# controllerboost.net
KiCad netlist of a schematic drawn in EAGLE
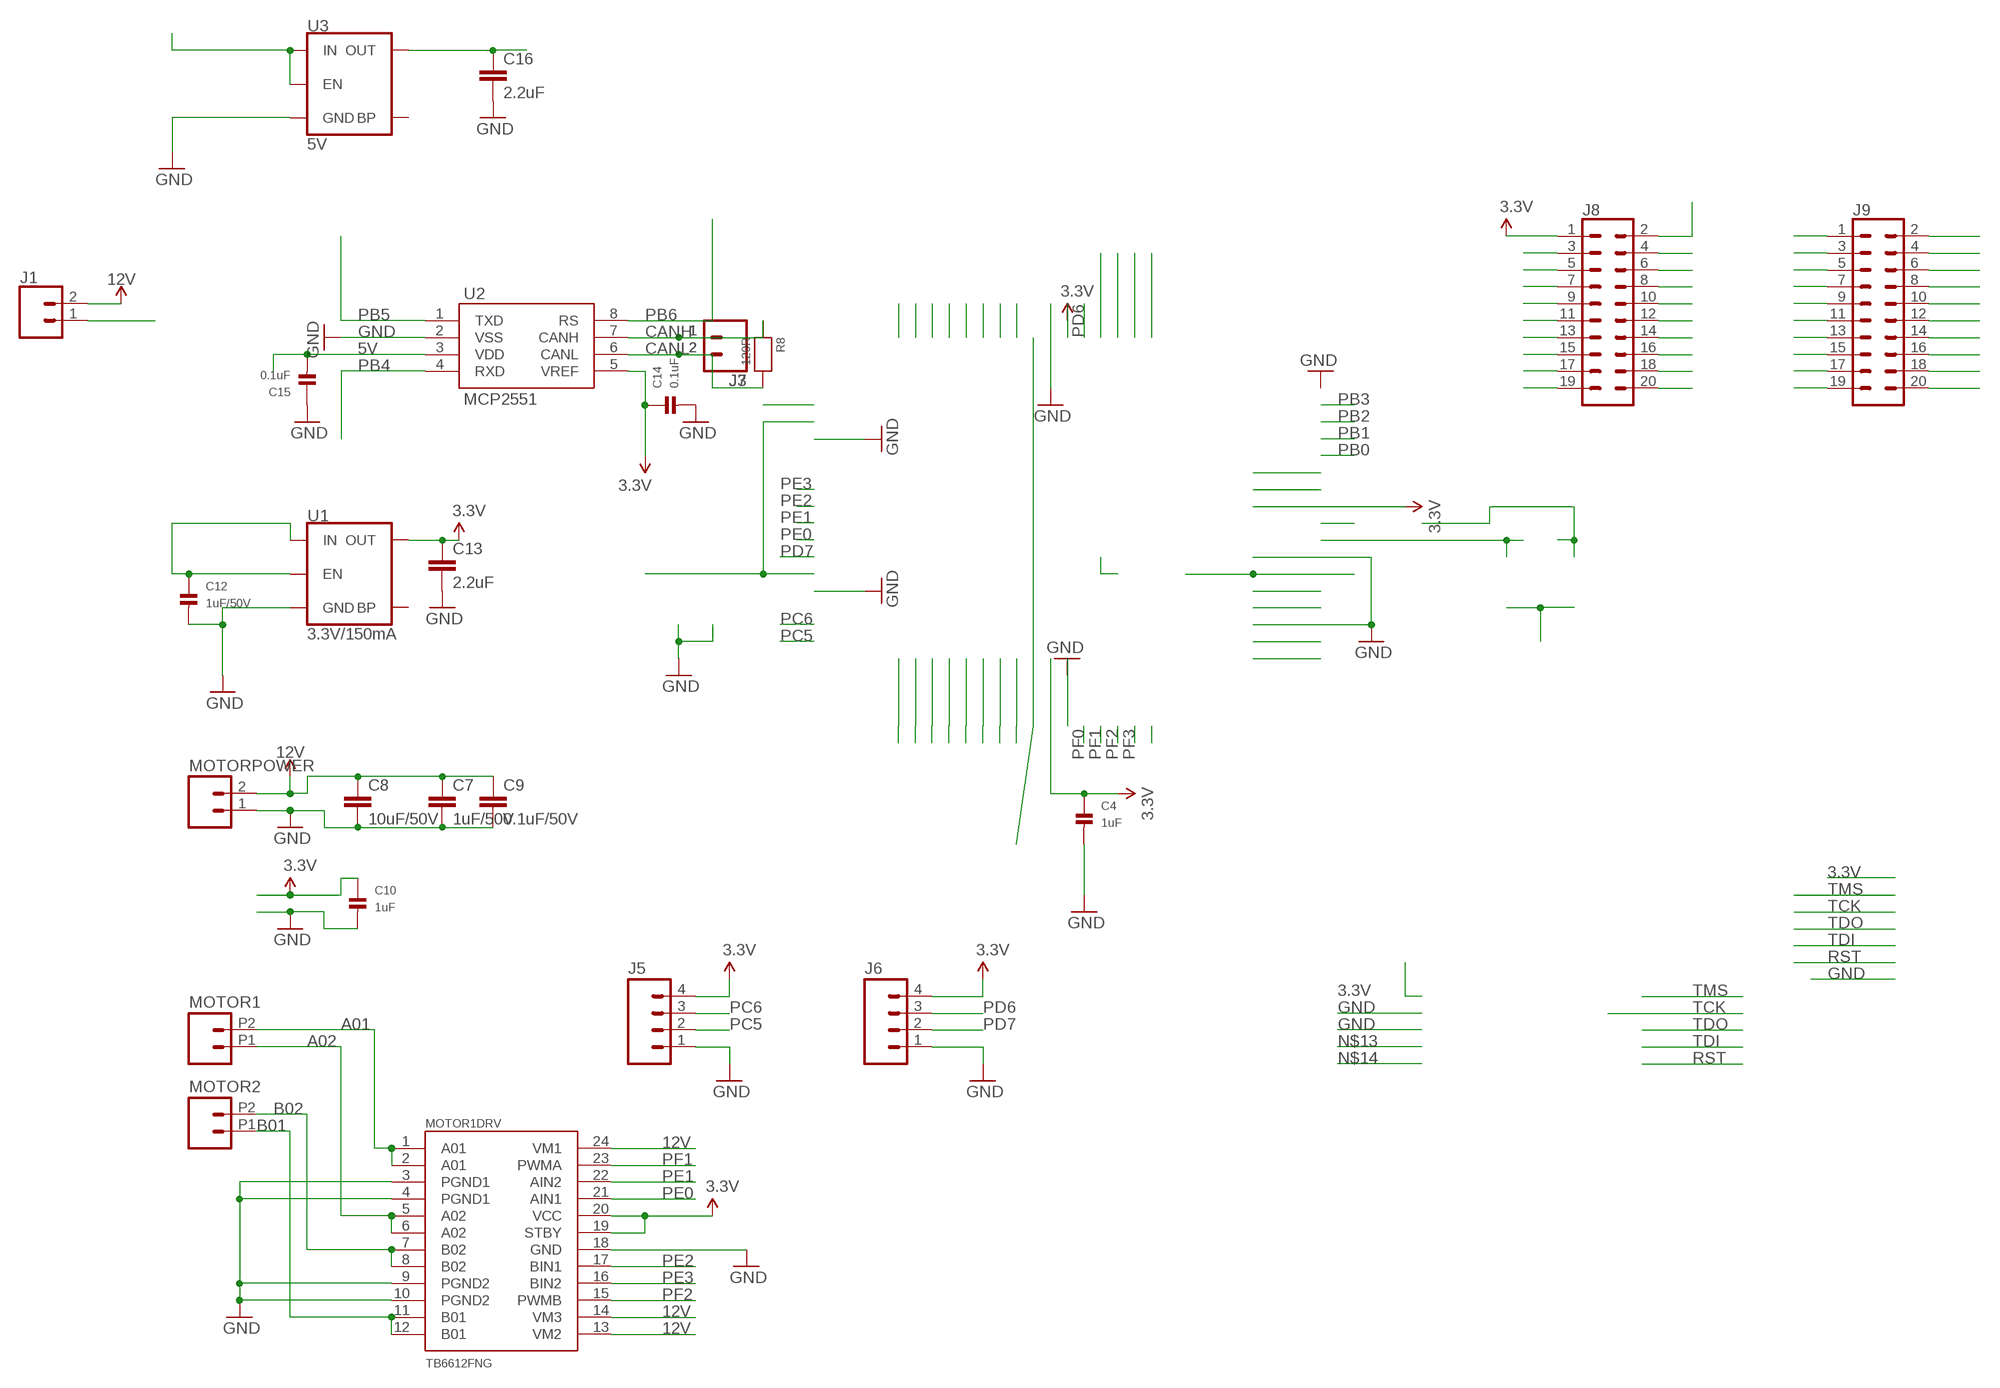
[diagram p0: schematic, sheet 1]

(export (version "E")
  (design (tool "Eeschema 10.0.6"))
  (components
    (comp (ref "C4")
      (value "1uF")
      (footprint "eagle-import:_0603MP")
      (libsource (lib "eagle-import") (part "CAP_CERAMIC_0603MP"))
    )
    (comp (ref "C7")
      (value "1uF/50V")
      (footprint "eagle-import:0603-CAP")
      (libsource (lib "eagle-import") (part "0.1UF-25V(+80/-20%)(0603)"))
    )
    (comp (ref "C8")
      (value "10uF/50V")
      (footprint "eagle-import:0805-CAP")
      (libsource (lib "eagle-import") (part "1.0UF-25V-+80/-20(0805){dblquote}"))
    )
    (comp (ref "C9")
      (value "0.1uF/50V")
      (footprint "eagle-import:0603-CAP")
      (libsource (lib "eagle-import") (part "0.1UF-25V(+80/-20%)(0603)"))
    )
    (comp (ref "C10")
      (value "1uF")
      (footprint "eagle-import:_0603MP")
      (libsource (lib "eagle-import") (part "CAP_CERAMIC_0603MP"))
    )
    (comp (ref "C12")
      (value "1uF/50V")
      (footprint "eagle-import:_0603MP")
      (libsource (lib "eagle-import") (part "CAP_CERAMIC_0603MP"))
    )
    (comp (ref "C13")
      (value "2.2uF")
      (footprint "eagle-import:0805")
      (libsource (lib "eagle-import") (part "2.2UF-0805-25V-(+80/-20%)"))
    )
    (comp (ref "C14")
      (value "0.1uF")
      (footprint "eagle-import:_0603MP")
      (libsource (lib "eagle-import") (part "CAP_CERAMIC_0603MP"))
    )
    (comp (ref "C15")
      (value "0.1uF")
      (footprint "eagle-import:_0603MP")
      (libsource (lib "eagle-import") (part "CAP_CERAMIC_0603MP"))
    )
    (comp (ref "C16")
      (value "2.2uF")
      (footprint "eagle-import:0805")
      (libsource (lib "eagle-import") (part "2.2UF-0805-25V-(+80/-20%)"))
    )
    (comp (ref "J1")
      (value "CONN_02")
      (footprint "eagle-import:1X02")
      (libsource (lib "eagle-import") (part "CONN_02"))
    )
    (comp (ref "J3")
      (value "CONN_02")
      (footprint "eagle-import:1X02")
      (libsource (lib "eagle-import") (part "CONN_02"))
    )
    (comp (ref "J5")
      (value "M04PTH")
      (footprint "eagle-import:1X04")
      (libsource (lib "eagle-import") (part "M04PTH"))
    )
    (comp (ref "J6")
      (value "M04PTH")
      (footprint "eagle-import:1X04")
      (libsource (lib "eagle-import") (part "M04PTH"))
    )
    (comp (ref "J7")
      (value "CONN_02")
      (footprint "eagle-import:1X02")
      (libsource (lib "eagle-import") (part "CONN_02"))
    )
    (comp (ref "J8")
      (value "CONN_10X2")
      (footprint "eagle-import:2X10")
      (libsource (lib "eagle-import") (part "CONN_10X2"))
    )
    (comp (ref "J9")
      (value "CONN_10X2")
      (footprint "eagle-import:2X10")
      (libsource (lib "eagle-import") (part "CONN_10X2"))
    )
    (comp (ref "MOTOR1")
      (value "M022.54MM_SCREWTERM")
      (footprint "eagle-import:1X02_2.54_SCREWTERM@1")
      (libsource (lib "eagle-import") (part "M022.54MM_SCREWTERM"))
    )
    (comp (ref "MOTOR1DRV")
      (value "TB6612FNG")
      (footprint "eagle-import:SSOP24")
      (libsource (lib "eagle-import") (part "TB6612FNG"))
    )
    (comp (ref "MOTOR2")
      (value "M022.54MM_SCREWTERM")
      (footprint "eagle-import:1X02_2.54_SCREWTERM@1")
      (libsource (lib "eagle-import") (part "M022.54MM_SCREWTERM"))
    )
    (comp (ref "MOTORPOWER")
      (value "M02PTH")
      (footprint "eagle-import:1X02@1")
      (libsource (lib "eagle-import") (part "M02PTH"))
    )
    (comp (ref "R8")
      (value "120R")
      (footprint "eagle-import:_0603MP")
      (libsource (lib "eagle-import") (part "RESISTOR_0603MP"))
    )
    (comp (ref "U1")
      (value "3.3V/150mA")
      (footprint "eagle-import:SOT23-5")
      (libsource (lib "eagle-import") (part "V_REG_MIC52053.3V"))
    )
    (comp (ref "U2")
      (value "MCP2551")
      (footprint "eagle-import:SO08")
      (libsource (lib "eagle-import") (part "MCP2551"))
    )
    (comp (ref "U3")
      (value "5V")
      (footprint "eagle-import:SOT23-5")
      (libsource (lib "eagle-import") (part "V_REG_MIC52053.3V"))
    )
  )
  (nets
    (net (code "1") (name "/5V") (class "Default")
      (node (ref "C15") (pin "2") (pinfunction "P$2_2") (pintype "passive"))
      (node (ref "C16") (pin "1") (pinfunction "1_1") (pintype "passive"))
      (node (ref "J8") (pin "2") (pinfunction "2_2") (pintype "passive"))
      (node (ref "U2") (pin "3") (pinfunction "VDD_3") (pintype "bidirectional"))
      (node (ref "U3") (pin "5") (pinfunction "OUT_5") (pintype "passive"))
    )
    (net (code "2") (name "/A01") (class "Default")
      (node (ref "MOTOR1") (pin "P2") (pinfunction "2_P2") (pintype "passive"))
      (node (ref "MOTOR1DRV") (pin "1") (pinfunction "A01_1") (pintype "bidirectional"))
      (node (ref "MOTOR1DRV") (pin "2") (pinfunction "A01_2") (pintype "bidirectional"))
    )
    (net (code "3") (name "/A02") (class "Default")
      (node (ref "MOTOR1") (pin "P1") (pinfunction "1_P1") (pintype "passive"))
      (node (ref "MOTOR1DRV") (pin "5") (pinfunction "A02_5") (pintype "bidirectional"))
      (node (ref "MOTOR1DRV") (pin "6") (pinfunction "A02_6") (pintype "bidirectional"))
    )
    (net (code "4") (name "/B01") (class "Default")
      (node (ref "MOTOR1DRV") (pin "11") (pinfunction "B01_11") (pintype "bidirectional"))
      (node (ref "MOTOR1DRV") (pin "12") (pinfunction "B01_12") (pintype "bidirectional"))
      (node (ref "MOTOR2") (pin "P1") (pinfunction "1_P1") (pintype "passive"))
    )
    (net (code "5") (name "/B02") (class "Default")
      (node (ref "MOTOR1DRV") (pin "7") (pinfunction "B02_7") (pintype "bidirectional"))
      (node (ref "MOTOR1DRV") (pin "8") (pinfunction "B02_8") (pintype "bidirectional"))
      (node (ref "MOTOR2") (pin "P2") (pinfunction "2_P2") (pintype "passive"))
    )
    (net (code "6") (name "/CANH") (class "Default")
      (node (ref "J3") (pin "1") (pinfunction "1_1") (pintype "passive"))
      (node (ref "J7") (pin "1") (pinfunction "1_1") (pintype "passive"))
      (node (ref "R8") (pin "1") (pinfunction "1_1") (pintype "passive"))
      (node (ref "U2") (pin "7") (pinfunction "CANH_7") (pintype "bidirectional"))
    )
    (net (code "7") (name "/CANL") (class "Default")
      (node (ref "J3") (pin "2") (pinfunction "2_2") (pintype "passive"))
      (node (ref "J7") (pin "2") (pinfunction "2_2") (pintype "passive"))
      (node (ref "R8") (pin "2") (pinfunction "2_2") (pintype "passive"))
      (node (ref "U2") (pin "6") (pinfunction "CANL_6") (pintype "bidirectional"))
    )
    (net (code "10") (name "/P2L") (class "Default")
      (node (ref "C12") (pin "1") (pinfunction "P$1_1") (pintype "passive"))
      (node (ref "J1") (pin "1") (pinfunction "1_1") (pintype "passive"))
      (node (ref "U1") (pin "1") (pinfunction "IN_1") (pintype "input"))
      (node (ref "U1") (pin "3") (pinfunction "EN_3") (pintype "input"))
      (node (ref "U3") (pin "1") (pinfunction "IN_1") (pintype "input"))
      (node (ref "U3") (pin "3") (pinfunction "EN_3") (pintype "input"))
    )
    (net (code "11") (name "/PB0") (class "Default")
      (node (ref "J8") (pin "5") (pinfunction "5_5") (pintype "passive"))
    )
    (net (code "12") (name "/PB1") (class "Default")
      (node (ref "J8") (pin "7") (pinfunction "7_7") (pintype "passive"))
    )
    (net (code "13") (name "/PB2") (class "Default")
      (node (ref "J9") (pin "4") (pinfunction "4_4") (pintype "passive"))
    )
    (net (code "14") (name "/PB3") (class "Default")
      (node (ref "J9") (pin "5") (pinfunction "5_5") (pintype "passive"))
    )
    (net (code "15") (name "/PB4") (class "Default")
      (node (ref "J8") (pin "13") (pinfunction "13_13") (pintype "passive"))
      (node (ref "U2") (pin "4") (pinfunction "RXD_4") (pintype "bidirectional"))
    )
    (net (code "16") (name "/PB5") (class "Default")
      (node (ref "J8") (pin "3") (pinfunction "3_3") (pintype "passive"))
      (node (ref "U2") (pin "1") (pinfunction "TXD_1") (pintype "bidirectional"))
    )
    (net (code "17") (name "/PB6") (class "Default")
      (node (ref "J9") (pin "14") (pinfunction "14_14") (pintype "passive"))
      (node (ref "U2") (pin "8") (pinfunction "RS_8") (pintype "bidirectional"))
    )
    (net (code "18") (name "/PC5") (class "Default")
      (node (ref "J5") (pin "2") (pinfunction "2_2") (pintype "passive"))
      (node (ref "J9") (pin "9") (pinfunction "9_9") (pintype "passive"))
    )
    (net (code "19") (name "/PC6") (class "Default")
      (node (ref "J5") (pin "3") (pinfunction "3_3") (pintype "passive"))
      (node (ref "J9") (pin "11") (pinfunction "11_11") (pintype "passive"))
    )
    (net (code "20") (name "/PD6") (class "Default")
      (node (ref "J6") (pin "3") (pinfunction "3_3") (pintype "passive"))
      (node (ref "J9") (pin "15") (pinfunction "15_15") (pintype "passive"))
    )
    (net (code "21") (name "/PD7") (class "Default")
      (node (ref "J6") (pin "2") (pinfunction "2_2") (pintype "passive"))
      (node (ref "J9") (pin "17") (pinfunction "17_17") (pintype "passive"))
    )
    (net (code "22") (name "/PE0") (class "Default")
      (node (ref "J9") (pin "6") (pinfunction "6_6") (pintype "passive"))
      (node (ref "MOTOR1DRV") (pin "21") (pinfunction "AIN1_21") (pintype "bidirectional"))
    )
    (net (code "23") (name "/PE1") (class "Default")
      (node (ref "J8") (pin "14") (pinfunction "14_14") (pintype "passive"))
      (node (ref "MOTOR1DRV") (pin "22") (pinfunction "AIN2_22") (pintype "bidirectional"))
    )
    (net (code "24") (name "/PE2") (class "Default")
      (node (ref "J8") (pin "16") (pinfunction "16_16") (pintype "passive"))
      (node (ref "MOTOR1DRV") (pin "17") (pinfunction "BIN1_17") (pintype "bidirectional"))
    )
    (net (code "25") (name "/PE3") (class "Default")
      (node (ref "J8") (pin "18") (pinfunction "18_18") (pintype "passive"))
      (node (ref "MOTOR1DRV") (pin "16") (pinfunction "BIN2_16") (pintype "bidirectional"))
    )
    (net (code "26") (name "/PF0") (class "Default")
      (node (ref "J9") (pin "8") (pinfunction "8_8") (pintype "passive"))
    )
    (net (code "27") (name "/PF1") (class "Default")
      (node (ref "J8") (pin "20") (pinfunction "20_20") (pintype "passive"))
      (node (ref "MOTOR1DRV") (pin "23") (pinfunction "PWMA_23") (pintype "bidirectional"))
    )
    (net (code "28") (name "/PF2") (class "Default")
      (node (ref "J9") (pin "1") (pinfunction "1_1") (pintype "passive"))
      (node (ref "MOTOR1DRV") (pin "15") (pinfunction "PWMB_15") (pintype "bidirectional"))
    )
    (net (code "29") (name "/PF3") (class "Default")
      (node (ref "J9") (pin "3") (pinfunction "3_3") (pintype "passive"))
    )
    (net (code "30") (name "/RST") (class "Default")
      (node (ref "J9") (pin "10") (pinfunction "10_10") (pintype "passive"))
    )
    (net (code "35") (name "3.3V") (class "Default")
      (node (ref "C10") (pin "1") (pinfunction "P$1_1") (pintype "passive"))
      (node (ref "C13") (pin "1") (pinfunction "1_1") (pintype "passive"))
      (node (ref "C14") (pin "1") (pinfunction "P$1_1") (pintype "passive"))
      (node (ref "C4") (pin "1") (pinfunction "P$1_1") (pintype "passive"))
      (node (ref "J5") (pin "4") (pinfunction "4_4") (pintype "passive"))
      (node (ref "J6") (pin "4") (pinfunction "4_4") (pintype "passive"))
      (node (ref "J8") (pin "1") (pinfunction "1_1") (pintype "passive"))
      (node (ref "MOTOR1DRV") (pin "19") (pinfunction "STBY_19") (pintype "bidirectional"))
      (node (ref "MOTOR1DRV") (pin "20") (pinfunction "VCC_20") (pintype "bidirectional"))
      (node (ref "U1") (pin "5") (pinfunction "OUT_5") (pintype "passive"))
      (node (ref "U2") (pin "5") (pinfunction "VREF_5") (pintype "bidirectional"))
    )
    (net (code "36") (name "12V") (class "Default")
      (node (ref "C7") (pin "1") (pinfunction "1_1") (pintype "passive"))
      (node (ref "C8") (pin "1") (pinfunction "1_1") (pintype "passive"))
      (node (ref "C9") (pin "1") (pinfunction "1_1") (pintype "passive"))
      (node (ref "J1") (pin "2") (pinfunction "2_2") (pintype "passive"))
      (node (ref "MOTOR1DRV") (pin "13") (pinfunction "VM2_13") (pintype "bidirectional"))
      (node (ref "MOTOR1DRV") (pin "14") (pinfunction "VM3_14") (pintype "bidirectional"))
      (node (ref "MOTOR1DRV") (pin "24") (pinfunction "VM1_24") (pintype "bidirectional"))
      (node (ref "MOTORPOWER") (pin "2") (pinfunction "2_2") (pintype "passive"))
    )
    (net (code "37") (name "GND") (class "Default")
      (node (ref "C10") (pin "2") (pinfunction "P$2_2") (pintype "passive"))
      (node (ref "C12") (pin "2") (pinfunction "P$2_2") (pintype "passive"))
      (node (ref "C13") (pin "2") (pinfunction "2_2") (pintype "passive"))
      (node (ref "C14") (pin "2") (pinfunction "P$2_2") (pintype "passive"))
      (node (ref "C15") (pin "1") (pinfunction "P$1_1") (pintype "passive"))
      (node (ref "C16") (pin "2") (pinfunction "2_2") (pintype "passive"))
      (node (ref "C4") (pin "2") (pinfunction "P$2_2") (pintype "passive"))
      (node (ref "C7") (pin "2") (pinfunction "2_2") (pintype "passive"))
      (node (ref "C8") (pin "2") (pinfunction "2_2") (pintype "passive"))
      (node (ref "C9") (pin "2") (pinfunction "2_2") (pintype "passive"))
      (node (ref "J5") (pin "1") (pinfunction "1_1") (pintype "passive"))
      (node (ref "J6") (pin "1") (pinfunction "1_1") (pintype "passive"))
      (node (ref "J8") (pin "4") (pinfunction "4_4") (pintype "passive"))
      (node (ref "J9") (pin "2") (pinfunction "2_2") (pintype "passive"))
      (node (ref "MOTOR1DRV") (pin "10") (pinfunction "PGND2_10") (pintype "bidirectional"))
      (node (ref "MOTOR1DRV") (pin "18") (pinfunction "GND_18") (pintype "bidirectional"))
      (node (ref "MOTOR1DRV") (pin "3") (pinfunction "PGND1_3") (pintype "bidirectional"))
      (node (ref "MOTOR1DRV") (pin "4") (pinfunction "PGND1_4") (pintype "bidirectional"))
      (node (ref "MOTOR1DRV") (pin "9") (pinfunction "PGND2_9") (pintype "bidirectional"))
      (node (ref "MOTORPOWER") (pin "1") (pinfunction "1_1") (pintype "passive"))
      (node (ref "U1") (pin "2") (pinfunction "GND_2") (pintype "input"))
      (node (ref "U2") (pin "2") (pinfunction "VSS_2") (pintype "bidirectional"))
      (node (ref "U3") (pin "2") (pinfunction "GND_2") (pintype "input"))
    )
    (net (code "38") (name "unconnected-(J8-Pad6)") (class "Default")
      (node (ref "J8") (pin "6") (pinfunction "6_6") (pintype "passive"))
    )
    (net (code "39") (name "unconnected-(J8-Pad8)") (class "Default")
      (node (ref "J8") (pin "8") (pinfunction "8_8") (pintype "passive"))
    )
    (net (code "40") (name "unconnected-(J8-Pad9)") (class "Default")
      (node (ref "J8") (pin "9") (pinfunction "9_9") (pintype "passive"))
    )
    (net (code "41") (name "unconnected-(J8-Pad10)") (class "Default")
      (node (ref "J8") (pin "10") (pinfunction "10_10") (pintype "passive"))
    )
    (net (code "42") (name "unconnected-(J8-Pad11)") (class "Default")
      (node (ref "J8") (pin "11") (pinfunction "11_11") (pintype "passive"))
    )
    (net (code "43") (name "unconnected-(J8-Pad12)") (class "Default")
      (node (ref "J8") (pin "12") (pinfunction "12_12") (pintype "passive"))
    )
    (net (code "44") (name "unconnected-(J8-Pad15)") (class "Default")
      (node (ref "J8") (pin "15") (pinfunction "15_15") (pintype "passive"))
    )
    (net (code "45") (name "unconnected-(J8-Pad17)") (class "Default")
      (node (ref "J8") (pin "17") (pinfunction "17_17") (pintype "passive"))
    )
    (net (code "46") (name "unconnected-(J8-Pad19)") (class "Default")
      (node (ref "J8") (pin "19") (pinfunction "19_19") (pintype "passive"))
    )
    (net (code "47") (name "unconnected-(J9-Pad7)") (class "Default")
      (node (ref "J9") (pin "7") (pinfunction "7_7") (pintype "passive"))
    )
    (net (code "48") (name "unconnected-(J9-Pad12)") (class "Default")
      (node (ref "J9") (pin "12") (pinfunction "12_12") (pintype "passive"))
    )
    (net (code "49") (name "unconnected-(J9-Pad13)") (class "Default")
      (node (ref "J9") (pin "13") (pinfunction "13_13") (pintype "passive"))
    )
    (net (code "50") (name "unconnected-(J9-Pad16)") (class "Default")
      (node (ref "J9") (pin "16") (pinfunction "16_16") (pintype "passive"))
    )
    (net (code "51") (name "unconnected-(J9-Pad18)") (class "Default")
      (node (ref "J9") (pin "18") (pinfunction "18_18") (pintype "passive"))
    )
    (net (code "52") (name "unconnected-(J9-Pad19)") (class "Default")
      (node (ref "J9") (pin "19") (pinfunction "19_19") (pintype "passive"))
    )
    (net (code "53") (name "unconnected-(J9-Pad20)") (class "Default")
      (node (ref "J9") (pin "20") (pinfunction "20_20") (pintype "passive"))
    )
    (net (code "54") (name "unconnected-(U1-BP-Pad4)") (class "Default")
      (node (ref "U1") (pin "4") (pinfunction "BP_4") (pintype "input"))
    )
    (net (code "55") (name "unconnected-(U3-BP-Pad4)") (class "Default")
      (node (ref "U3") (pin "4") (pinfunction "BP_4") (pintype "input"))
    )
  )
)
